# GMSK_Prototyping_Board.net
KiCad netlist of a schematic drawn in Altium Designer
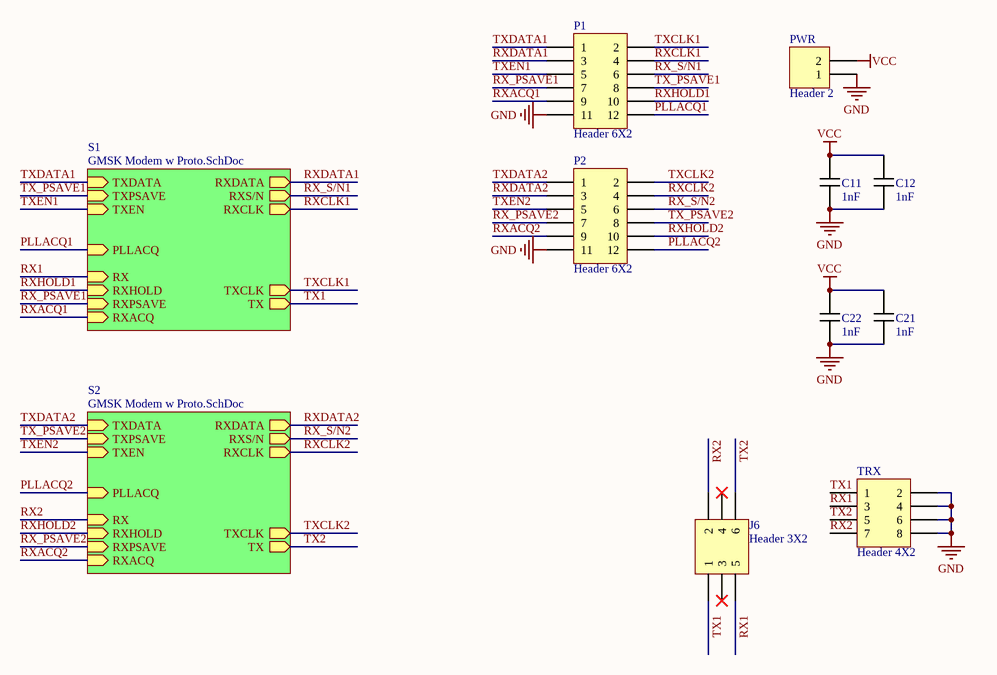
[diagram p0: GMSK Prototyping Board.SchDoc]

(export (version "E")
  (design (tool "Eeschema 10.0.6"))
  (components
    (comp (ref "C11")
      (value "1nF")
      (footprint "0805 Cap")
      (description "0805 MLCC - X7R, 10%")
      (fields (field (name "Comment") "0805 Cap"))
      (libsource (lib "GMSK Prototyping Board") (part "0805 MLCC - X7R, 10%"))
    )
    (comp (ref "C12")
      (value "1nF")
      (footprint "0805 Cap")
      (description "0805 MLCC - X7R, 10%")
      (fields (field (name "Comment") "0805 Cap"))
      (libsource (lib "GMSK Prototyping Board") (part "0805 MLCC - X7R, 10%"))
    )
    (comp (ref "C21")
      (value "1nF")
      (footprint "0805 Cap")
      (description "0805 MLCC - X7R, 10%")
      (fields (field (name "Comment") "0805 Cap"))
      (libsource (lib "GMSK Prototyping Board") (part "0805 MLCC - X7R, 10%"))
    )
    (comp (ref "C22")
      (value "1nF")
      (footprint "0805 Cap")
      (description "0805 MLCC - X7R, 10%")
      (fields (field (name "Comment") "0805 Cap"))
      (libsource (lib "GMSK Prototyping Board") (part "0805 MLCC - X7R, 10%"))
    )
    (comp (ref "J6")
      (value "Header 3X2")
      (footprint "HDR2X3")
      (description "Header, 3-Pin, Dual row")
      (fields (field (name "PUBLISHER") "Altium Limited"))
      (libsource (lib "GMSK Prototyping Board") (part "Header 3X2"))
    )
    (comp (ref "P1")
      (value "Header 6X2")
      (footprint "HDR2X6")
      (description "Header, 6-Pin, Dual row")
      (fields (field (name "PUBLISHER") "Altium Limited"))
      (libsource (lib "GMSK Prototyping Board") (part "Header 6X2"))
    )
    (comp (ref "P2")
      (value "Header 6X2")
      (footprint "HDR2X6")
      (description "Header, 6-Pin, Dual row")
      (fields (field (name "PUBLISHER") "Altium Limited"))
      (libsource (lib "GMSK Prototyping Board") (part "Header 6X2"))
    )
    (comp (ref "PWR")
      (value "Header 2")
      (footprint "HDR1X2")
      (description "Header, 2-Pin")
      (fields (field (name "PUBLISHER") "Altium Limited"))
      (libsource (lib "GMSK Prototyping Board") (part "Header 2"))
    )
    (comp (ref "TRX")
      (value "Header 4X2")
      (footprint "HDR2X4")
      (description "Header, 4-Pin, Dual row")
      (fields (field (name "PUBLISHER") "Altium Limited"))
      (libsource (lib "GMSK Prototyping Board") (part "Header 4X2"))
    )
  )
  (nets
    (net (code "1") (name "/PLLACQ1") (class "Default")
      (node (ref "P1") (pin "12") (pinfunction "12_12") (pintype "passive"))
    )
    (net (code "2") (name "/PLLACQ2") (class "Default")
      (node (ref "P2") (pin "12") (pinfunction "12_12") (pintype "passive"))
    )
    (net (code "3") (name "/RX1") (class "Default")
      (node (ref "J6") (pin "5") (pinfunction "5_5") (pintype "passive"))
      (node (ref "TRX") (pin "3") (pinfunction "3_3") (pintype "passive"))
    )
    (net (code "4") (name "/RX2") (class "Default")
      (node (ref "J6") (pin "2") (pinfunction "2_2") (pintype "passive"))
      (node (ref "TRX") (pin "7") (pinfunction "7_7") (pintype "passive"))
    )
    (net (code "5") (name "/RXACQ1") (class "Default")
      (node (ref "P1") (pin "9") (pinfunction "9_9") (pintype "passive"))
    )
    (net (code "6") (name "/RXACQ2") (class "Default")
      (node (ref "P2") (pin "9") (pinfunction "9_9") (pintype "passive"))
    )
    (net (code "7") (name "/RXCLK1") (class "Default")
      (node (ref "P1") (pin "4") (pinfunction "4_4") (pintype "passive"))
    )
    (net (code "8") (name "/RXCLK2") (class "Default")
      (node (ref "P2") (pin "4") (pinfunction "4_4") (pintype "passive"))
    )
    (net (code "9") (name "/RXDATA1") (class "Default")
      (node (ref "P1") (pin "3") (pinfunction "3_3") (pintype "passive"))
    )
    (net (code "10") (name "/RXDATA2") (class "Default")
      (node (ref "P2") (pin "3") (pinfunction "3_3") (pintype "passive"))
    )
    (net (code "11") (name "/RXHOLD1") (class "Default")
      (node (ref "P1") (pin "10") (pinfunction "10_10") (pintype "passive"))
    )
    (net (code "12") (name "/RXHOLD2") (class "Default")
      (node (ref "P2") (pin "10") (pinfunction "10_10") (pintype "passive"))
    )
    (net (code "13") (name "/RX_PSAVE1") (class "Default")
      (node (ref "P1") (pin "7") (pinfunction "7_7") (pintype "passive"))
    )
    (net (code "14") (name "/RX_PSAVE2") (class "Default")
      (node (ref "P2") (pin "7") (pinfunction "7_7") (pintype "passive"))
    )
    (net (code "15") (name "/RX_S{slash}N1") (class "Default")
      (node (ref "P1") (pin "6") (pinfunction "6_6") (pintype "passive"))
    )
    (net (code "16") (name "/RX_S{slash}N2") (class "Default")
      (node (ref "P2") (pin "6") (pinfunction "6_6") (pintype "passive"))
    )
    (net (code "17") (name "/TX1") (class "Default")
      (node (ref "J6") (pin "1") (pinfunction "1_1") (pintype "passive"))
      (node (ref "TRX") (pin "1") (pinfunction "1_1") (pintype "passive"))
    )
    (net (code "18") (name "/TX2") (class "Default")
      (node (ref "J6") (pin "6") (pinfunction "6_6") (pintype "passive"))
      (node (ref "TRX") (pin "5") (pinfunction "5_5") (pintype "passive"))
    )
    (net (code "19") (name "/TXCLK1") (class "Default")
      (node (ref "P1") (pin "2") (pinfunction "2_2") (pintype "passive"))
    )
    (net (code "20") (name "/TXCLK2") (class "Default")
      (node (ref "P2") (pin "2") (pinfunction "2_2") (pintype "passive"))
    )
    (net (code "21") (name "/TXDATA1") (class "Default")
      (node (ref "P1") (pin "1") (pinfunction "1_1") (pintype "passive"))
    )
    (net (code "22") (name "/TXDATA2") (class "Default")
      (node (ref "P2") (pin "1") (pinfunction "1_1") (pintype "passive"))
    )
    (net (code "23") (name "/TXEN1") (class "Default")
      (node (ref "P1") (pin "5") (pinfunction "5_5") (pintype "passive"))
    )
    (net (code "24") (name "/TXEN2") (class "Default")
      (node (ref "P2") (pin "5") (pinfunction "5_5") (pintype "passive"))
    )
    (net (code "25") (name "/TX_PSAVE1") (class "Default")
      (node (ref "P1") (pin "8") (pinfunction "8_8") (pintype "passive"))
    )
    (net (code "26") (name "/TX_PSAVE2") (class "Default")
      (node (ref "P2") (pin "8") (pinfunction "8_8") (pintype "passive"))
    )
    (net (code "27") (name "GND") (class "Default")
      (node (ref "C11") (pin "2") (pinfunction "2_2") (pintype "passive"))
      (node (ref "C12") (pin "2") (pinfunction "2_2") (pintype "passive"))
      (node (ref "C21") (pin "1") (pinfunction "1_1") (pintype "passive"))
      (node (ref "C22") (pin "1") (pinfunction "1_1") (pintype "passive"))
      (node (ref "P1") (pin "11") (pinfunction "11_11") (pintype "passive"))
      (node (ref "P2") (pin "11") (pinfunction "11_11") (pintype "passive"))
      (node (ref "PWR") (pin "1") (pinfunction "1_1") (pintype "passive"))
      (node (ref "TRX") (pin "2") (pinfunction "2_2") (pintype "passive"))
      (node (ref "TRX") (pin "4") (pinfunction "4_4") (pintype "passive"))
      (node (ref "TRX") (pin "6") (pinfunction "6_6") (pintype "passive"))
      (node (ref "TRX") (pin "8") (pinfunction "8_8") (pintype "passive"))
    )
    (net (code "28") (name "VCC") (class "Default")
      (node (ref "C11") (pin "1") (pinfunction "1_1") (pintype "passive"))
      (node (ref "C12") (pin "1") (pinfunction "1_1") (pintype "passive"))
      (node (ref "C21") (pin "2") (pinfunction "2_2") (pintype "passive"))
      (node (ref "C22") (pin "2") (pinfunction "2_2") (pintype "passive"))
      (node (ref "PWR") (pin "2") (pinfunction "2_2") (pintype "passive"))
    )
    (net (code "29") (name "unconnected-(J6-Pad3)") (class "Default")
      (node (ref "J6") (pin "3") (pinfunction "3_3") (pintype "passive+no_connect"))
    )
    (net (code "30") (name "unconnected-(J6-Pad4)") (class "Default")
      (node (ref "J6") (pin "4") (pinfunction "4_4") (pintype "passive+no_connect"))
    )
  )
)
